# wheelSense_revB.net
KiCad netlist of a schematic drawn in EAGLE
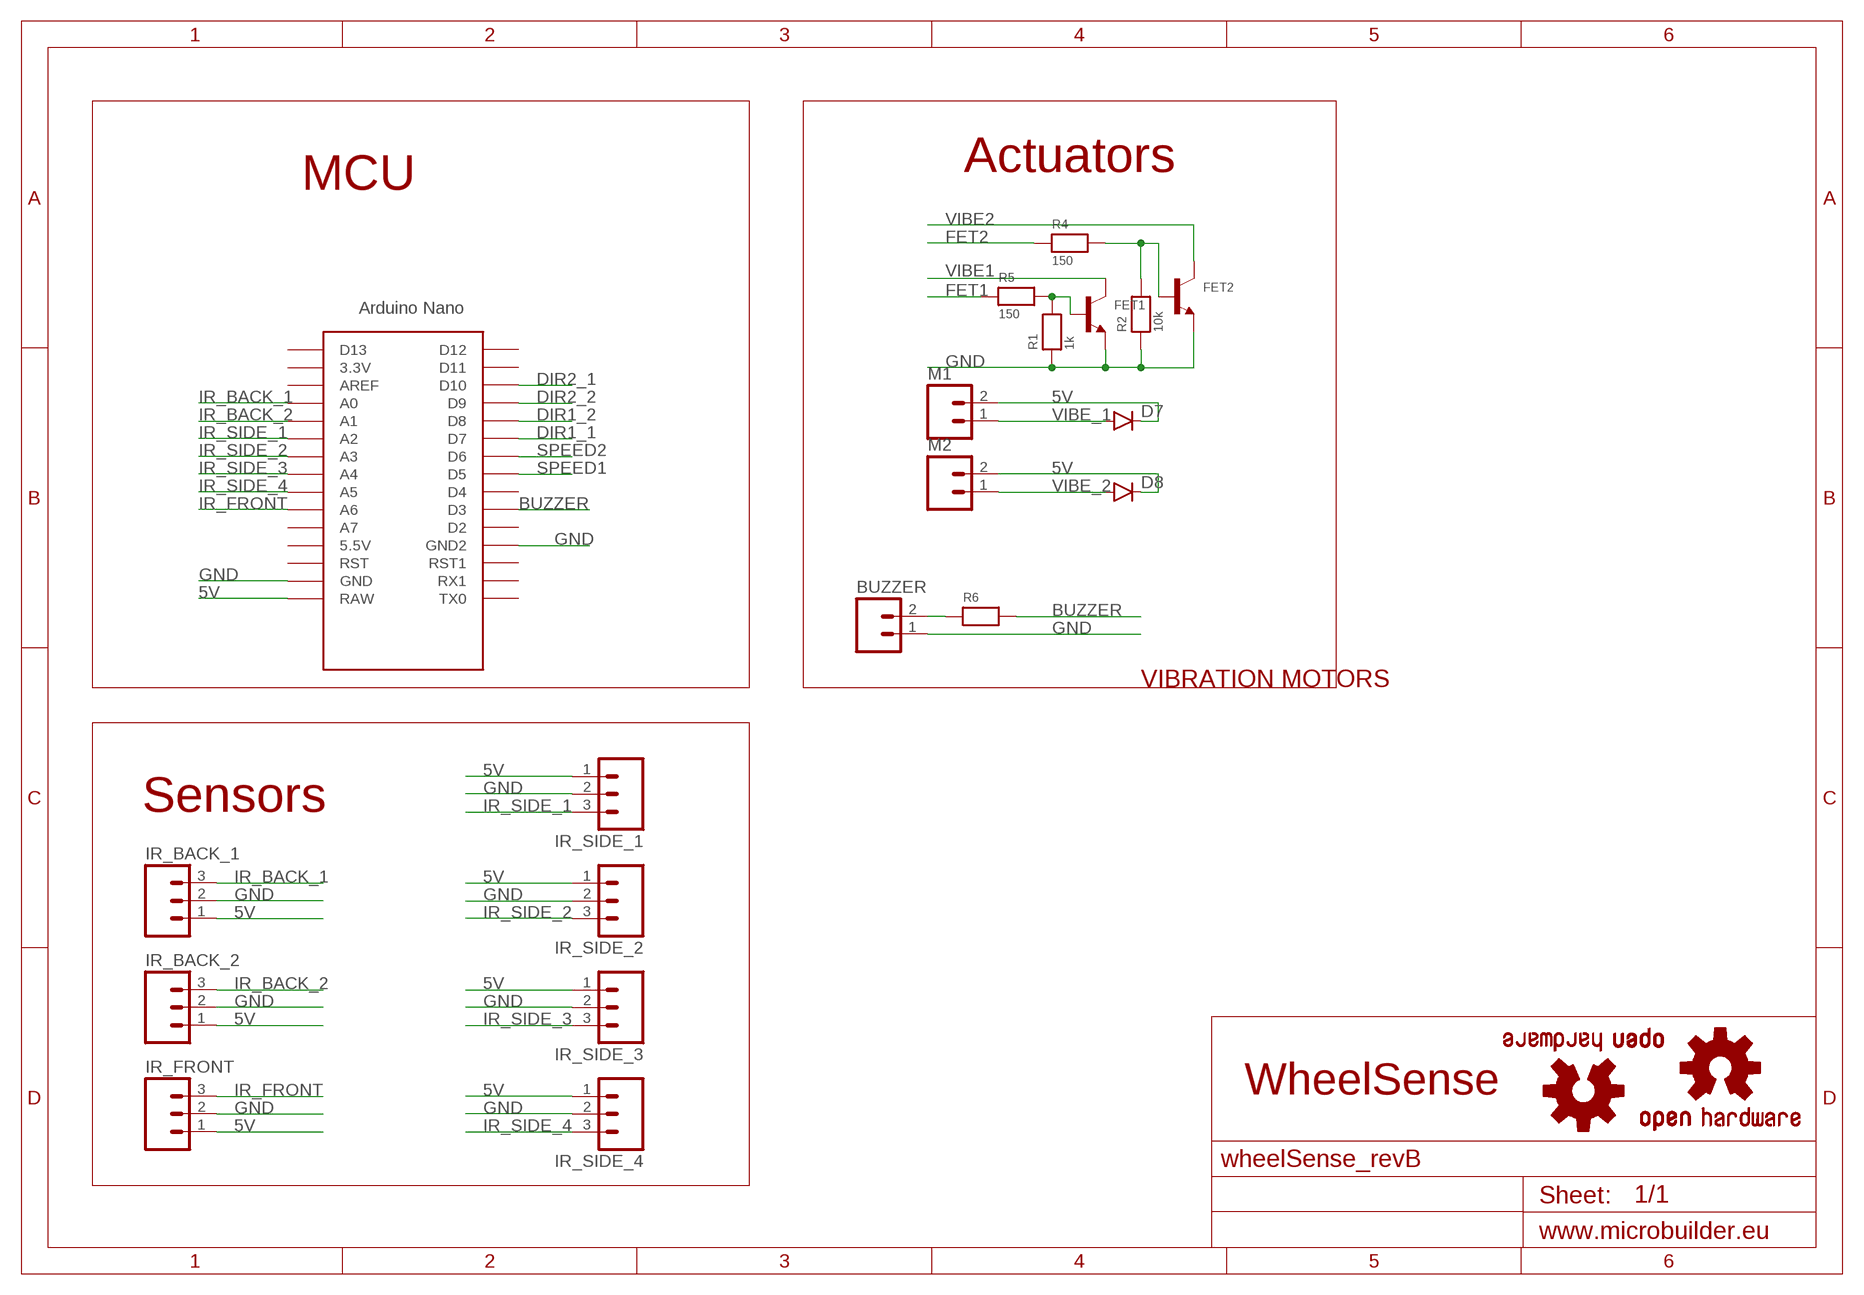
[diagram p0: schematic, sheet 1]

(export (version "E")
  (design (tool "Eeschema 10.0.6"))
  (components
    (comp (ref "BUZZER")
      (value "M02POLAR")
      (footprint "eagle-import:MOLEX-1X2")
      (libsource (lib "eagle-import") (part "M02POLAR"))
    )
    (comp (ref "D7")
      (value "DIODESOD123")
      (footprint "eagle-import:SOD-123")
      (libsource (lib "eagle-import") (part "DIODESOD123"))
    )
    (comp (ref "D8")
      (value "DIODESOD123")
      (footprint "eagle-import:SOD-123")
      (libsource (lib "eagle-import") (part "DIODESOD123"))
    )
    (comp (ref "FET1")
      (value "TRANSISTOR_NPN")
      (footprint "eagle-import:SOT23-R")
      (libsource (lib "eagle-import") (part "TRANSISTOR_NPN"))
    )
    (comp (ref "FET2")
      (value "TRANSISTOR_NPN")
      (footprint "eagle-import:SOT23-R")
      (libsource (lib "eagle-import") (part "TRANSISTOR_NPN"))
    )
    (comp (ref "IR_BACK_1")
      (value "M03POLAR")
      (footprint "eagle-import:MOLEX-1X3")
      (libsource (lib "eagle-import") (part "M03POLAR"))
    )
    (comp (ref "IR_BACK_2")
      (value "M03POLAR")
      (footprint "eagle-import:MOLEX-1X3")
      (libsource (lib "eagle-import") (part "M03POLAR"))
    )
    (comp (ref "IR_FRONT")
      (value "M03POLAR")
      (footprint "eagle-import:MOLEX-1X3")
      (libsource (lib "eagle-import") (part "M03POLAR"))
    )
    (comp (ref "IR_SIDE_1")
      (value "M03POLAR")
      (footprint "eagle-import:MOLEX-1X3")
      (libsource (lib "eagle-import") (part "M03POLAR"))
    )
    (comp (ref "IR_SIDE_2")
      (value "M03POLAR")
      (footprint "eagle-import:MOLEX-1X3")
      (libsource (lib "eagle-import") (part "M03POLAR"))
    )
    (comp (ref "IR_SIDE_3")
      (value "M03POLAR")
      (footprint "eagle-import:MOLEX-1X3")
      (libsource (lib "eagle-import") (part "M03POLAR"))
    )
    (comp (ref "IR_SIDE_4")
      (value "M03POLAR")
      (footprint "eagle-import:MOLEX-1X3")
      (libsource (lib "eagle-import") (part "M03POLAR"))
    )
    (comp (ref "LOGO1")
      (value "OSHW-LOGOL-TOP")
      (footprint "eagle-import:OSHW_LOGO_L_TOP")
      (libsource (lib "eagle-import") (part "OSHW-LOGOL-TOP"))
    )
    (comp (ref "LOGO2")
      (value "OSHW-LOGOL-TOP")
      (footprint "eagle-import:OSHW_LOGO_L_TOP")
      (libsource (lib "eagle-import") (part "OSHW-LOGOL-TOP"))
    )
    (comp (ref "M1")
      (value "M02POLAR")
      (footprint "eagle-import:MOLEX-1X2")
      (libsource (lib "eagle-import") (part "M02POLAR"))
    )
    (comp (ref "M2")
      (value "M02POLAR")
      (footprint "eagle-import:MOLEX-1X2")
      (libsource (lib "eagle-import") (part "M02POLAR"))
    )
    (comp (ref "R1")
      (value "1k")
      (footprint "eagle-import:0805")
      (libsource (lib "eagle-import") (part "RESISTOR0805"))
    )
    (comp (ref "R2")
      (value "10k")
      (footprint "eagle-import:0805")
      (libsource (lib "eagle-import") (part "RESISTOR0805"))
    )
    (comp (ref "R4")
      (value "150")
      (footprint "eagle-import:0805")
      (libsource (lib "eagle-import") (part "RESISTOR0805"))
    )
    (comp (ref "R5")
      (value "150")
      (footprint "eagle-import:0805")
      (libsource (lib "eagle-import") (part "RESISTOR0805"))
    )
    (comp (ref "R6")
      (value "RESISTOR0805")
      (footprint "eagle-import:0805")
      (libsource (lib "eagle-import") (part "RESISTOR0805"))
    )
    (comp (ref "U$1")
      (value "NANO")
      (footprint "eagle-import:NANO")
      (libsource (lib "eagle-import") (part "NANO"))
    )
  )
  (nets
    (net (code "1") (name "/5V") (class "Default")
      (node (ref "D7") (pin "C") (pinfunction "C_C") (pintype "passive"))
      (node (ref "D8") (pin "C") (pinfunction "C_C") (pintype "passive"))
      (node (ref "IR_BACK_1") (pin "1") (pinfunction "1_1") (pintype "passive"))
      (node (ref "IR_BACK_2") (pin "1") (pinfunction "1_1") (pintype "passive"))
      (node (ref "IR_FRONT") (pin "1") (pinfunction "1_1") (pintype "passive"))
      (node (ref "IR_SIDE_1") (pin "1") (pinfunction "1_1") (pintype "passive"))
      (node (ref "IR_SIDE_2") (pin "1") (pinfunction "1_1") (pintype "passive"))
      (node (ref "IR_SIDE_3") (pin "1") (pinfunction "1_1") (pintype "passive"))
      (node (ref "IR_SIDE_4") (pin "1") (pinfunction "1_1") (pintype "passive"))
      (node (ref "M1") (pin "2") (pinfunction "2_2") (pintype "passive"))
      (node (ref "M2") (pin "2") (pinfunction "2_2") (pintype "passive"))
      (node (ref "U$1") (pin "RAW") (pinfunction "RAW_RAW") (pintype "bidirectional"))
    )
    (net (code "2") (name "/BUZZER") (class "Default")
      (node (ref "R6") (pin "2") (pinfunction "2_2") (pintype "passive"))
      (node (ref "U$1") (pin "D3") (pinfunction "D3_D3") (pintype "bidirectional"))
    )
    (net (code "3") (name "/DIR1_1") (class "Default")
      (node (ref "U$1") (pin "D7") (pinfunction "D7_D7") (pintype "bidirectional"))
    )
    (net (code "4") (name "/DIR1_2") (class "Default")
      (node (ref "U$1") (pin "D8") (pinfunction "D8_D8") (pintype "bidirectional"))
    )
    (net (code "5") (name "/DIR2_1") (class "Default")
      (node (ref "U$1") (pin "D10") (pinfunction "D10_D10") (pintype "bidirectional"))
    )
    (net (code "6") (name "/DIR2_2") (class "Default")
      (node (ref "U$1") (pin "D9") (pinfunction "D9_D9") (pintype "bidirectional"))
    )
    (net (code "7") (name "/FET1") (class "Default")
      (node (ref "R5") (pin "1") (pinfunction "1_1") (pintype "passive"))
    )
    (net (code "8") (name "/FET2") (class "Default")
      (node (ref "R4") (pin "1") (pinfunction "1_1") (pintype "passive"))
    )
    (net (code "9") (name "/GND") (class "Default")
      (node (ref "BUZZER") (pin "1") (pinfunction "1_1") (pintype "passive"))
      (node (ref "FET1") (pin "2") (pinfunction "E_2") (pintype "passive"))
      (node (ref "FET2") (pin "2") (pinfunction "E_2") (pintype "passive"))
      (node (ref "IR_BACK_1") (pin "2") (pinfunction "2_2") (pintype "passive"))
      (node (ref "IR_BACK_2") (pin "2") (pinfunction "2_2") (pintype "passive"))
      (node (ref "IR_FRONT") (pin "2") (pinfunction "2_2") (pintype "passive"))
      (node (ref "IR_SIDE_1") (pin "2") (pinfunction "2_2") (pintype "passive"))
      (node (ref "IR_SIDE_2") (pin "2") (pinfunction "2_2") (pintype "passive"))
      (node (ref "IR_SIDE_3") (pin "2") (pinfunction "2_2") (pintype "passive"))
      (node (ref "IR_SIDE_4") (pin "2") (pinfunction "2_2") (pintype "passive"))
      (node (ref "R1") (pin "1") (pinfunction "1_1") (pintype "passive"))
      (node (ref "R2") (pin "1") (pinfunction "1_1") (pintype "passive"))
      (node (ref "U$1") (pin "GND") (pinfunction "GND_GND") (pintype "bidirectional"))
      (node (ref "U$1") (pin "GND1") (pinfunction "GND2_GND1") (pintype "bidirectional"))
    )
    (net (code "10") (name "/IR_BACK_1") (class "Default")
      (node (ref "IR_BACK_1") (pin "3") (pinfunction "3_3") (pintype "passive"))
      (node (ref "U$1") (pin "A0") (pinfunction "A0_A0") (pintype "bidirectional"))
    )
    (net (code "11") (name "/IR_BACK_2") (class "Default")
      (node (ref "IR_BACK_2") (pin "3") (pinfunction "3_3") (pintype "passive"))
      (node (ref "U$1") (pin "A1") (pinfunction "A1_A1") (pintype "bidirectional"))
    )
    (net (code "12") (name "/IR_FRONT") (class "Default")
      (node (ref "IR_FRONT") (pin "3") (pinfunction "3_3") (pintype "passive"))
      (node (ref "U$1") (pin "A6") (pinfunction "A6_A6") (pintype "bidirectional"))
    )
    (net (code "13") (name "/IR_SIDE_1") (class "Default")
      (node (ref "IR_SIDE_1") (pin "3") (pinfunction "3_3") (pintype "passive"))
      (node (ref "U$1") (pin "A2") (pinfunction "A2_A2") (pintype "bidirectional"))
    )
    (net (code "14") (name "/IR_SIDE_2") (class "Default")
      (node (ref "IR_SIDE_2") (pin "3") (pinfunction "3_3") (pintype "passive"))
      (node (ref "U$1") (pin "A3") (pinfunction "A3_A3") (pintype "bidirectional"))
    )
    (net (code "15") (name "/IR_SIDE_3") (class "Default")
      (node (ref "IR_SIDE_3") (pin "3") (pinfunction "3_3") (pintype "passive"))
      (node (ref "U$1") (pin "A4") (pinfunction "A4_A4") (pintype "bidirectional"))
    )
    (net (code "16") (name "/IR_SIDE_4") (class "Default")
      (node (ref "IR_SIDE_4") (pin "3") (pinfunction "3_3") (pintype "passive"))
      (node (ref "U$1") (pin "A5") (pinfunction "A5_A5") (pintype "bidirectional"))
    )
    (net (code "17") (name "/SPEED1") (class "Default")
      (node (ref "U$1") (pin "D5") (pinfunction "D5_D5") (pintype "bidirectional"))
    )
    (net (code "18") (name "/SPEED2") (class "Default")
      (node (ref "U$1") (pin "D6") (pinfunction "D6_D6") (pintype "bidirectional"))
    )
    (net (code "19") (name "/VIBE1") (class "Default")
      (node (ref "FET1") (pin "3") (pinfunction "C_3") (pintype "passive"))
    )
    (net (code "20") (name "/VIBE2") (class "Default")
      (node (ref "FET2") (pin "3") (pinfunction "C_3") (pintype "passive"))
    )
    (net (code "21") (name "/VIBE_1") (class "Default")
      (node (ref "D7") (pin "A") (pinfunction "A_A") (pintype "passive"))
      (node (ref "M1") (pin "1") (pinfunction "1_1") (pintype "passive"))
    )
    (net (code "22") (name "/VIBE_2") (class "Default")
      (node (ref "D8") (pin "A") (pinfunction "A_A") (pintype "passive"))
      (node (ref "M2") (pin "1") (pinfunction "1_1") (pintype "passive"))
    )
    (net (code "23") (name "Net-(BUZZER-Pad2)") (class "Default")
      (node (ref "BUZZER") (pin "2") (pinfunction "2_2") (pintype "passive"))
      (node (ref "R6") (pin "1") (pinfunction "1_1") (pintype "passive"))
    )
    (net (code "24") (name "Net-(FET1-B)") (class "Default")
      (node (ref "FET1") (pin "1") (pinfunction "B_1") (pintype "passive"))
      (node (ref "R1") (pin "2") (pinfunction "2_2") (pintype "passive"))
      (node (ref "R5") (pin "2") (pinfunction "2_2") (pintype "passive"))
    )
    (net (code "25") (name "Net-(FET2-B)") (class "Default")
      (node (ref "FET2") (pin "1") (pinfunction "B_1") (pintype "passive"))
      (node (ref "R2") (pin "2") (pinfunction "2_2") (pintype "passive"))
      (node (ref "R4") (pin "2") (pinfunction "2_2") (pintype "passive"))
    )
    (net (code "26") (name "unconnected-(U$1-5.5V-Pad5V)") (class "Default")
      (node (ref "U$1") (pin "5V") (pinfunction "5.5V_5V") (pintype "bidirectional"))
    )
    (net (code "27") (name "unconnected-(U$1-Pad3.3V)") (class "Default")
      (node (ref "U$1") (pin "3.3V") (pinfunction "3.3V_3.3V") (pintype "bidirectional"))
    )
    (net (code "28") (name "unconnected-(U$1-PadA7)") (class "Default")
      (node (ref "U$1") (pin "A7") (pinfunction "A7_A7") (pintype "bidirectional"))
    )
    (net (code "29") (name "unconnected-(U$1-PadAREF)") (class "Default")
      (node (ref "U$1") (pin "AREF") (pinfunction "AREF_AREF") (pintype "bidirectional"))
    )
    (net (code "30") (name "unconnected-(U$1-PadD2)") (class "Default")
      (node (ref "U$1") (pin "D2") (pinfunction "D2_D2") (pintype "bidirectional"))
    )
    (net (code "31") (name "unconnected-(U$1-PadD4)") (class "Default")
      (node (ref "U$1") (pin "D4") (pinfunction "D4_D4") (pintype "bidirectional"))
    )
    (net (code "32") (name "unconnected-(U$1-PadD11)") (class "Default")
      (node (ref "U$1") (pin "D11") (pinfunction "D11_D11") (pintype "bidirectional"))
    )
    (net (code "33") (name "unconnected-(U$1-PadD12)") (class "Default")
      (node (ref "U$1") (pin "D12") (pinfunction "D12_D12") (pintype "bidirectional"))
    )
    (net (code "34") (name "unconnected-(U$1-PadD13)") (class "Default")
      (node (ref "U$1") (pin "D13") (pinfunction "D13_D13") (pintype "bidirectional"))
    )
    (net (code "35") (name "unconnected-(U$1-PadICSP1)") (class "Default")
      (node (ref "U$1") (pin "ICSP1") (pinfunction "ICSP1_ICSP1") (pintype "bidirectional"))
    )
    (net (code "36") (name "unconnected-(U$1-PadICSP2)") (class "Default")
      (node (ref "U$1") (pin "ICSP2") (pinfunction "ICSP2_ICSP2") (pintype "bidirectional"))
    )
    (net (code "37") (name "unconnected-(U$1-PadICSP3)") (class "Default")
      (node (ref "U$1") (pin "ICSP3") (pinfunction "ICSP3_ICSP3") (pintype "bidirectional"))
    )
    (net (code "38") (name "unconnected-(U$1-PadICSP4)") (class "Default")
      (node (ref "U$1") (pin "ICSP4") (pinfunction "ICSP4_ICSP4") (pintype "bidirectional"))
    )
    (net (code "39") (name "unconnected-(U$1-PadICSP5)") (class "Default")
      (node (ref "U$1") (pin "ICSP5") (pinfunction "ICSP5_ICSP5") (pintype "bidirectional"))
    )
    (net (code "40") (name "unconnected-(U$1-PadICSP6)") (class "Default")
      (node (ref "U$1") (pin "ICSP6") (pinfunction "ICSP6_ICSP6") (pintype "bidirectional"))
    )
    (net (code "41") (name "unconnected-(U$1-PadRST)") (class "Default")
      (node (ref "U$1") (pin "RST") (pinfunction "RST_RST") (pintype "bidirectional"))
    )
    (net (code "42") (name "unconnected-(U$1-PadRST1)") (class "Default")
      (node (ref "U$1") (pin "RST1") (pinfunction "RST1_RST1") (pintype "bidirectional"))
    )
    (net (code "43") (name "unconnected-(U$1-PadRX1)") (class "Default")
      (node (ref "U$1") (pin "RX1") (pinfunction "RX1_RX1") (pintype "bidirectional"))
    )
    (net (code "44") (name "unconnected-(U$1-PadTX0)") (class "Default")
      (node (ref "U$1") (pin "TX0") (pinfunction "TX0_TX0") (pintype "bidirectional"))
    )
  )
)
